# Power.net
KiCad netlist of a schematic drawn in EAGLE
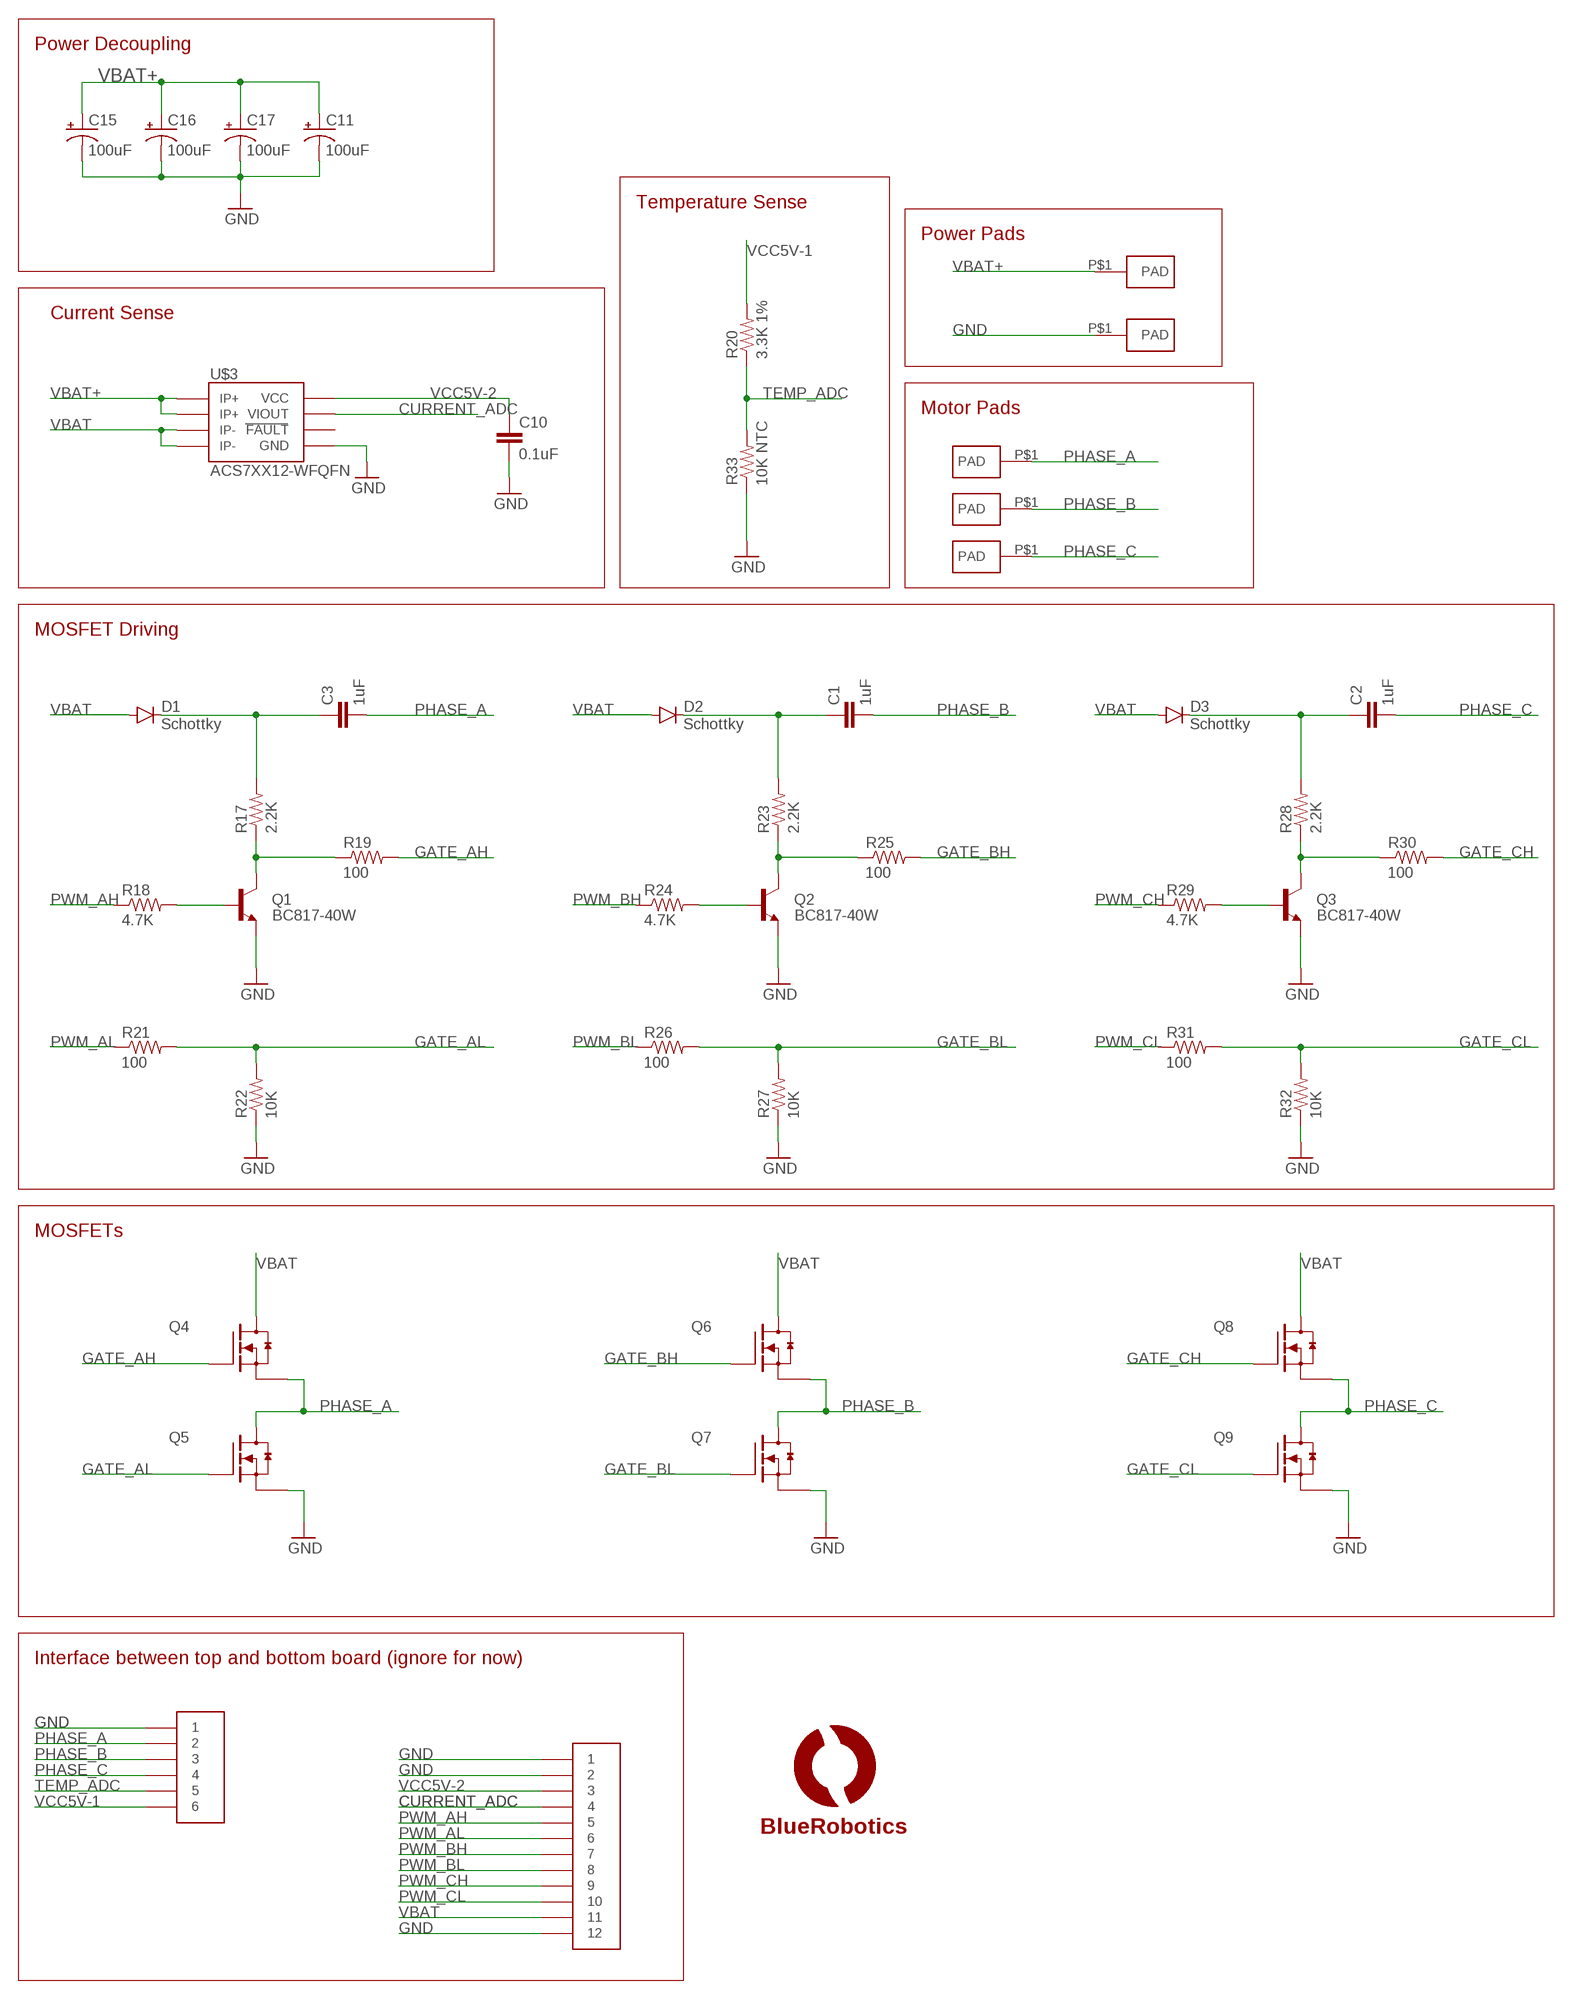
[diagram p0: schematic, sheet 1]

(export (version "E")
  (design (tool "Eeschema 10.0.6"))
  (components
    (comp (ref "C1")
      (value "1uF")
      (footprint "eagle-import:0805")
      (libsource (lib "eagle-import") (part "CAP0805"))
    )
    (comp (ref "C2")
      (value "1uF")
      (footprint "eagle-import:0805")
      (libsource (lib "eagle-import") (part "CAP0805"))
    )
    (comp (ref "C3")
      (value "1uF")
      (footprint "eagle-import:0805")
      (libsource (lib "eagle-import") (part "CAP0805"))
    )
    (comp (ref "C10")
      (value "0.1uF")
      (footprint "eagle-import:0603-CAP")
      (libsource (lib "eagle-import") (part "CAP0603-CAP"))
    )
    (comp (ref "C11")
      (value "100uF")
      (footprint "eagle-import:EIA7343")
      (libsource (lib "eagle-import") (part "CAP_POL7343"))
    )
    (comp (ref "C15")
      (value "100uF")
      (footprint "eagle-import:EIA7343")
      (libsource (lib "eagle-import") (part "CAP_POL7343"))
    )
    (comp (ref "C16")
      (value "100uF")
      (footprint "eagle-import:EIA7343")
      (libsource (lib "eagle-import") (part "CAP_POL7343"))
    )
    (comp (ref "C17")
      (value "100uF")
      (footprint "eagle-import:EIA7343")
      (libsource (lib "eagle-import") (part "CAP_POL7343"))
    )
    (comp (ref "D1")
      (value "Schottky")
      (footprint "eagle-import:SOD-323")
      (libsource (lib "eagle-import") (part "DIODESOD"))
    )
    (comp (ref "D2")
      (value "Schottky")
      (footprint "eagle-import:SOD-323")
      (libsource (lib "eagle-import") (part "DIODESOD"))
    )
    (comp (ref "D3")
      (value "Schottky")
      (footprint "eagle-import:SOD-323")
      (libsource (lib "eagle-import") (part "DIODESOD"))
    )
    (comp (ref "Q1")
      (value "BC817-40W")
      (footprint "eagle-import:SOT23")
      (libsource (lib "eagle-import") (part "TRANSISTOR_NPNSOT23"))
    )
    (comp (ref "Q2")
      (value "BC817-40W")
      (footprint "eagle-import:SOT23")
      (libsource (lib "eagle-import") (part "TRANSISTOR_NPNSOT23"))
    )
    (comp (ref "Q3")
      (value "BC817-40W")
      (footprint "eagle-import:SOT23")
      (libsource (lib "eagle-import") (part "TRANSISTOR_NPNSOT23"))
    )
    (comp (ref "Q4")
      (value "SI7370")
      (footprint "eagle-import:POWERPAK-SO-08")
      (libsource (lib "eagle-import") (part "SI7370"))
    )
    (comp (ref "Q5")
      (value "SI7370")
      (footprint "eagle-import:POWERPAK-SO-08")
      (libsource (lib "eagle-import") (part "SI7370"))
    )
    (comp (ref "Q6")
      (value "SI7370")
      (footprint "eagle-import:POWERPAK-SO-08")
      (libsource (lib "eagle-import") (part "SI7370"))
    )
    (comp (ref "Q7")
      (value "SI7370")
      (footprint "eagle-import:POWERPAK-SO-08")
      (libsource (lib "eagle-import") (part "SI7370"))
    )
    (comp (ref "Q8")
      (value "SI7370")
      (footprint "eagle-import:POWERPAK-SO-08")
      (libsource (lib "eagle-import") (part "SI7370"))
    )
    (comp (ref "Q9")
      (value "SI7370")
      (footprint "eagle-import:POWERPAK-SO-08")
      (libsource (lib "eagle-import") (part "SI7370"))
    )
    (comp (ref "R17")
      (value "2.2K")
      (footprint "eagle-import:0603-RES")
      (libsource (lib "eagle-import") (part "33KOHM1/10W1%(0603)"))
    )
    (comp (ref "R18")
      (value "4.7K")
      (footprint "eagle-import:0603-RES")
      (libsource (lib "eagle-import") (part "33KOHM1/10W1%(0603)"))
    )
    (comp (ref "R19")
      (value "100")
      (footprint "eagle-import:0603-RES")
      (libsource (lib "eagle-import") (part "33KOHM1/10W1%(0603)"))
    )
    (comp (ref "R20")
      (value "3.3K 1%")
      (footprint "eagle-import:0603-RES")
      (libsource (lib "eagle-import") (part "33KOHM1/10W1%(0603)"))
    )
    (comp (ref "R21")
      (value "100")
      (footprint "eagle-import:0603-RES")
      (libsource (lib "eagle-import") (part "33KOHM1/10W1%(0603)"))
    )
    (comp (ref "R22")
      (value "10K")
      (footprint "eagle-import:0603-RES")
      (libsource (lib "eagle-import") (part "33KOHM1/10W1%(0603)"))
    )
    (comp (ref "R23")
      (value "2.2K")
      (footprint "eagle-import:0603-RES")
      (libsource (lib "eagle-import") (part "33KOHM1/10W1%(0603)"))
    )
    (comp (ref "R24")
      (value "4.7K")
      (footprint "eagle-import:0603-RES")
      (libsource (lib "eagle-import") (part "33KOHM1/10W1%(0603)"))
    )
    (comp (ref "R25")
      (value "100")
      (footprint "eagle-import:0603-RES")
      (libsource (lib "eagle-import") (part "33KOHM1/10W1%(0603)"))
    )
    (comp (ref "R26")
      (value "100")
      (footprint "eagle-import:0603-RES")
      (libsource (lib "eagle-import") (part "33KOHM1/10W1%(0603)"))
    )
    (comp (ref "R27")
      (value "10K")
      (footprint "eagle-import:0603-RES")
      (libsource (lib "eagle-import") (part "33KOHM1/10W1%(0603)"))
    )
    (comp (ref "R28")
      (value "2.2K")
      (footprint "eagle-import:0603-RES")
      (libsource (lib "eagle-import") (part "33KOHM1/10W1%(0603)"))
    )
    (comp (ref "R29")
      (value "4.7K")
      (footprint "eagle-import:0603-RES")
      (libsource (lib "eagle-import") (part "33KOHM1/10W1%(0603)"))
    )
    (comp (ref "R30")
      (value "100")
      (footprint "eagle-import:0603-RES")
      (libsource (lib "eagle-import") (part "33KOHM1/10W1%(0603)"))
    )
    (comp (ref "R31")
      (value "100")
      (footprint "eagle-import:0603-RES")
      (libsource (lib "eagle-import") (part "33KOHM1/10W1%(0603)"))
    )
    (comp (ref "R32")
      (value "10K")
      (footprint "eagle-import:0603-RES")
      (libsource (lib "eagle-import") (part "33KOHM1/10W1%(0603)"))
    )
    (comp (ref "R33")
      (value "10K NTC")
      (footprint "eagle-import:0603-RES")
      (libsource (lib "eagle-import") (part "33KOHM1/10W1%(0603)"))
    )
    (comp (ref "U$1")
      (value "PADPTH-MED")
      (footprint "eagle-import:PAD-PTH-MED-1")
      (libsource (lib "eagle-import") (part "PADPTH-MED"))
    )
    (comp (ref "U$2")
      (value "PADPTH-MED")
      (footprint "eagle-import:PAD-PTH-MED-1")
      (libsource (lib "eagle-import") (part "PADPTH-MED"))
    )
    (comp (ref "U$3")
      (value "ACS7XX12-WFQFN")
      (footprint "eagle-import:12-WFQFN")
      (libsource (lib "eagle-import") (part "ACS7XX12-WFQFN"))
    )
    (comp (ref "U$4")
      (value "HEADER-62MM")
      (footprint "eagle-import:HEADER-2MM-6POS")
      (libsource (lib "eagle-import") (part "HEADER-62MM"))
    )
    (comp (ref "U$5")
      (value "PAD18AWG")
      (footprint "eagle-import:PAD-PTH-18AWG-1")
      (libsource (lib "eagle-import") (part "PAD18AWG"))
    )
    (comp (ref "U$6")
      (value "PAD18AWG")
      (footprint "eagle-import:PAD-PTH-18AWG-1")
      (libsource (lib "eagle-import") (part "PAD18AWG"))
    )
    (comp (ref "U$7")
      (value "PAD18AWG")
      (footprint "eagle-import:PAD-PTH-18AWG-1")
      (libsource (lib "eagle-import") (part "PAD18AWG"))
    )
    (comp (ref "U$8")
      (value "HEADER-122MM")
      (footprint "eagle-import:HEADER-2MM-12POS")
      (libsource (lib "eagle-import") (part "HEADER-122MM"))
    )
    (comp (ref "U$9")
      (value "LOGOBR-LOGO-S")
      (footprint "eagle-import:BR-LOGO-SMALL")
      (libsource (lib "eagle-import") (part "LOGOBR-LOGO-S"))
    )
  )
  (nets
    (net (code "1") (name "/CURRENT_ADC") (class "Default")
      (node (ref "U$3") (pin "VIOUT") (pinfunction "VIOUT_VIOUT") (pintype "bidirectional"))
      (node (ref "U$8") (pin "P$4") (pinfunction "4_P$4") (pintype "bidirectional"))
    )
    (net (code "2") (name "/GATE_AH") (class "Default")
      (node (ref "Q4") (pin "4") (pinfunction "G_4") (pintype "passive"))
      (node (ref "R19") (pin "2") (pinfunction "2_2") (pintype "passive"))
    )
    (net (code "3") (name "/GATE_AL") (class "Default")
      (node (ref "Q5") (pin "4") (pinfunction "G_4") (pintype "passive"))
      (node (ref "R21") (pin "2") (pinfunction "2_2") (pintype "passive"))
      (node (ref "R22") (pin "2") (pinfunction "2_2") (pintype "passive"))
    )
    (net (code "4") (name "/GATE_BH") (class "Default")
      (node (ref "Q6") (pin "4") (pinfunction "G_4") (pintype "passive"))
      (node (ref "R25") (pin "2") (pinfunction "2_2") (pintype "passive"))
    )
    (net (code "5") (name "/GATE_BL") (class "Default")
      (node (ref "Q7") (pin "4") (pinfunction "G_4") (pintype "passive"))
      (node (ref "R26") (pin "2") (pinfunction "2_2") (pintype "passive"))
      (node (ref "R27") (pin "2") (pinfunction "2_2") (pintype "passive"))
    )
    (net (code "6") (name "/GATE_CH") (class "Default")
      (node (ref "Q8") (pin "4") (pinfunction "G_4") (pintype "passive"))
      (node (ref "R30") (pin "2") (pinfunction "2_2") (pintype "passive"))
    )
    (net (code "7") (name "/GATE_CL") (class "Default")
      (node (ref "Q9") (pin "4") (pinfunction "G_4") (pintype "passive"))
      (node (ref "R31") (pin "2") (pinfunction "2_2") (pintype "passive"))
      (node (ref "R32") (pin "2") (pinfunction "2_2") (pintype "passive"))
    )
    (net (code "8") (name "/PHASE_A") (class "Default")
      (node (ref "C3") (pin "2") (pinfunction "2_2") (pintype "passive"))
      (node (ref "Q4") (pin "3") (pinfunction "S3_3") (pintype "passive"))
      (node (ref "Q5") (pin "5-8") (pinfunction "D_5-8") (pintype "passive"))
      (node (ref "U$4") (pin "P$2") (pinfunction "2_P$2") (pintype "bidirectional"))
      (node (ref "U$5") (pin "P$1") (pinfunction "PAD_P$1") (pintype "bidirectional"))
    )
    (net (code "9") (name "/PHASE_B") (class "Default")
      (node (ref "C1") (pin "2") (pinfunction "2_2") (pintype "passive"))
      (node (ref "Q6") (pin "3") (pinfunction "S3_3") (pintype "passive"))
      (node (ref "Q7") (pin "5-8") (pinfunction "D_5-8") (pintype "passive"))
      (node (ref "U$4") (pin "P$3") (pinfunction "3_P$3") (pintype "bidirectional"))
      (node (ref "U$6") (pin "P$1") (pinfunction "PAD_P$1") (pintype "bidirectional"))
    )
    (net (code "10") (name "/PHASE_C") (class "Default")
      (node (ref "C2") (pin "2") (pinfunction "2_2") (pintype "passive"))
      (node (ref "Q8") (pin "3") (pinfunction "S3_3") (pintype "passive"))
      (node (ref "Q9") (pin "5-8") (pinfunction "D_5-8") (pintype "passive"))
      (node (ref "U$4") (pin "P$4") (pinfunction "4_P$4") (pintype "bidirectional"))
      (node (ref "U$7") (pin "P$1") (pinfunction "PAD_P$1") (pintype "bidirectional"))
    )
    (net (code "11") (name "/PWM_AH") (class "Default")
      (node (ref "R18") (pin "1") (pinfunction "1_1") (pintype "passive"))
      (node (ref "U$8") (pin "P$5") (pinfunction "5_P$5") (pintype "bidirectional"))
    )
    (net (code "12") (name "/PWM_AL") (class "Default")
      (node (ref "R21") (pin "1") (pinfunction "1_1") (pintype "passive"))
      (node (ref "U$8") (pin "P$6") (pinfunction "6_P$6") (pintype "bidirectional"))
    )
    (net (code "13") (name "/PWM_BH") (class "Default")
      (node (ref "R24") (pin "1") (pinfunction "1_1") (pintype "passive"))
      (node (ref "U$8") (pin "P$7") (pinfunction "7_P$7") (pintype "bidirectional"))
    )
    (net (code "14") (name "/PWM_BL") (class "Default")
      (node (ref "R26") (pin "1") (pinfunction "1_1") (pintype "passive"))
      (node (ref "U$8") (pin "P$8") (pinfunction "8_P$8") (pintype "bidirectional"))
    )
    (net (code "15") (name "/PWM_CH") (class "Default")
      (node (ref "R29") (pin "1") (pinfunction "1_1") (pintype "passive"))
      (node (ref "U$8") (pin "P$9") (pinfunction "9_P$9") (pintype "bidirectional"))
    )
    (net (code "16") (name "/PWM_CL") (class "Default")
      (node (ref "R31") (pin "1") (pinfunction "1_1") (pintype "passive"))
      (node (ref "U$8") (pin "P$10") (pinfunction "10_P$10") (pintype "bidirectional"))
    )
    (net (code "17") (name "/TEMP_ADC") (class "Default")
      (node (ref "R20") (pin "1") (pinfunction "1_1") (pintype "passive"))
      (node (ref "R33") (pin "2") (pinfunction "2_2") (pintype "passive"))
      (node (ref "U$4") (pin "P$5") (pinfunction "5_P$5") (pintype "bidirectional"))
    )
    (net (code "18") (name "/VBAT") (class "Default")
      (node (ref "D1") (pin "A") (pinfunction "A_A") (pintype "passive"))
      (node (ref "D2") (pin "A") (pinfunction "A_A") (pintype "passive"))
      (node (ref "D3") (pin "A") (pinfunction "A_A") (pintype "passive"))
      (node (ref "Q4") (pin "5-8") (pinfunction "D_5-8") (pintype "passive"))
      (node (ref "Q6") (pin "5-8") (pinfunction "D_5-8") (pintype "passive"))
      (node (ref "Q8") (pin "5-8") (pinfunction "D_5-8") (pintype "passive"))
      (node (ref "U$3") (pin "IP-1") (pinfunction "IP-1_IP-1") (pintype "bidirectional"))
      (node (ref "U$3") (pin "IP-2") (pinfunction "IP-2_IP-2") (pintype "bidirectional"))
      (node (ref "U$8") (pin "P$11") (pinfunction "11_P$11") (pintype "bidirectional"))
    )
    (net (code "19") (name "/VBAT+") (class "Default")
      (node (ref "C11") (pin "A") (pinfunction "+_A") (pintype "passive"))
      (node (ref "C15") (pin "A") (pinfunction "+_A") (pintype "passive"))
      (node (ref "C16") (pin "A") (pinfunction "+_A") (pintype "passive"))
      (node (ref "C17") (pin "A") (pinfunction "+_A") (pintype "passive"))
      (node (ref "U$1") (pin "P$1") (pinfunction "PAD_P$1") (pintype "bidirectional"))
      (node (ref "U$3") (pin "IP+1") (pinfunction "IP+1_IP+1") (pintype "bidirectional"))
      (node (ref "U$3") (pin "IP+2") (pinfunction "IP+2_IP+2") (pintype "bidirectional"))
    )
    (net (code "20") (name "/VCC5V-1") (class "Default")
      (node (ref "R20") (pin "2") (pinfunction "2_2") (pintype "passive"))
      (node (ref "U$4") (pin "P$6") (pinfunction "6_P$6") (pintype "bidirectional"))
    )
    (net (code "21") (name "/VCC5V-2") (class "Default")
      (node (ref "C10") (pin "1") (pinfunction "1_1") (pintype "passive"))
      (node (ref "U$3") (pin "VCC") (pinfunction "VCC_VCC") (pintype "power_in"))
      (node (ref "U$8") (pin "P$3") (pinfunction "3_P$3") (pintype "bidirectional"))
    )
    (net (code "22") (name "GND") (class "Default")
      (node (ref "C10") (pin "2") (pinfunction "2_2") (pintype "passive"))
      (node (ref "C11") (pin "C") (pinfunction "-_C") (pintype "passive"))
      (node (ref "C15") (pin "C") (pinfunction "-_C") (pintype "passive"))
      (node (ref "C16") (pin "C") (pinfunction "-_C") (pintype "passive"))
      (node (ref "C17") (pin "C") (pinfunction "-_C") (pintype "passive"))
      (node (ref "Q1") (pin "2") (pinfunction "E_2") (pintype "passive"))
      (node (ref "Q2") (pin "2") (pinfunction "E_2") (pintype "passive"))
      (node (ref "Q3") (pin "2") (pinfunction "E_2") (pintype "passive"))
      (node (ref "Q5") (pin "3") (pinfunction "S3_3") (pintype "passive"))
      (node (ref "Q7") (pin "3") (pinfunction "S3_3") (pintype "passive"))
      (node (ref "Q9") (pin "3") (pinfunction "S3_3") (pintype "passive"))
      (node (ref "R22") (pin "1") (pinfunction "1_1") (pintype "passive"))
      (node (ref "R27") (pin "1") (pinfunction "1_1") (pintype "passive"))
      (node (ref "R32") (pin "1") (pinfunction "1_1") (pintype "passive"))
      (node (ref "R33") (pin "1") (pinfunction "1_1") (pintype "passive"))
      (node (ref "U$2") (pin "P$1") (pinfunction "PAD_P$1") (pintype "bidirectional"))
      (node (ref "U$3") (pin "GND") (pinfunction "GND_GND") (pintype "power_in"))
      (node (ref "U$4") (pin "P$1") (pinfunction "1_P$1") (pintype "bidirectional"))
      (node (ref "U$8") (pin "P$1") (pinfunction "1_P$1") (pintype "bidirectional"))
      (node (ref "U$8") (pin "P$12") (pinfunction "12_P$12") (pintype "bidirectional"))
      (node (ref "U$8") (pin "P$2") (pinfunction "2_P$2") (pintype "bidirectional"))
    )
    (net (code "23") (name "Net-(C1-Pad1)") (class "Default")
      (node (ref "C1") (pin "1") (pinfunction "1_1") (pintype "passive"))
      (node (ref "D2") (pin "C") (pinfunction "C_C") (pintype "passive"))
      (node (ref "R23") (pin "2") (pinfunction "2_2") (pintype "passive"))
    )
    (net (code "24") (name "Net-(C2-Pad1)") (class "Default")
      (node (ref "C2") (pin "1") (pinfunction "1_1") (pintype "passive"))
      (node (ref "D3") (pin "C") (pinfunction "C_C") (pintype "passive"))
      (node (ref "R28") (pin "2") (pinfunction "2_2") (pintype "passive"))
    )
    (net (code "25") (name "Net-(C3-Pad1)") (class "Default")
      (node (ref "C3") (pin "1") (pinfunction "1_1") (pintype "passive"))
      (node (ref "D1") (pin "C") (pinfunction "C_C") (pintype "passive"))
      (node (ref "R17") (pin "2") (pinfunction "2_2") (pintype "passive"))
    )
    (net (code "26") (name "Net-(Q1-B)") (class "Default")
      (node (ref "Q1") (pin "1") (pinfunction "B_1") (pintype "passive"))
      (node (ref "R18") (pin "2") (pinfunction "2_2") (pintype "passive"))
    )
    (net (code "27") (name "Net-(Q1-C)") (class "Default")
      (node (ref "Q1") (pin "3") (pinfunction "C_3") (pintype "passive"))
      (node (ref "R17") (pin "1") (pinfunction "1_1") (pintype "passive"))
      (node (ref "R19") (pin "1") (pinfunction "1_1") (pintype "passive"))
    )
    (net (code "28") (name "Net-(Q2-B)") (class "Default")
      (node (ref "Q2") (pin "1") (pinfunction "B_1") (pintype "passive"))
      (node (ref "R24") (pin "2") (pinfunction "2_2") (pintype "passive"))
    )
    (net (code "29") (name "Net-(Q2-C)") (class "Default")
      (node (ref "Q2") (pin "3") (pinfunction "C_3") (pintype "passive"))
      (node (ref "R23") (pin "1") (pinfunction "1_1") (pintype "passive"))
      (node (ref "R25") (pin "1") (pinfunction "1_1") (pintype "passive"))
    )
    (net (code "30") (name "Net-(Q3-B)") (class "Default")
      (node (ref "Q3") (pin "1") (pinfunction "B_1") (pintype "passive"))
      (node (ref "R29") (pin "2") (pinfunction "2_2") (pintype "passive"))
    )
    (net (code "31") (name "Net-(Q3-C)") (class "Default")
      (node (ref "Q3") (pin "3") (pinfunction "C_3") (pintype "passive"))
      (node (ref "R28") (pin "1") (pinfunction "1_1") (pintype "passive"))
      (node (ref "R30") (pin "1") (pinfunction "1_1") (pintype "passive"))
    )
    (net (code "32") (name "unconnected-(Q4-S1-Pad1)") (class "Default")
      (node (ref "Q4") (pin "1") (pinfunction "S1_1") (pintype "passive"))
    )
    (net (code "33") (name "unconnected-(Q4-S2-Pad2)") (class "Default")
      (node (ref "Q4") (pin "2") (pinfunction "S2_2") (pintype "passive"))
    )
    (net (code "34") (name "unconnected-(Q5-S1-Pad1)") (class "Default")
      (node (ref "Q5") (pin "1") (pinfunction "S1_1") (pintype "passive"))
    )
    (net (code "35") (name "unconnected-(Q5-S2-Pad2)") (class "Default")
      (node (ref "Q5") (pin "2") (pinfunction "S2_2") (pintype "passive"))
    )
    (net (code "36") (name "unconnected-(Q6-S1-Pad1)") (class "Default")
      (node (ref "Q6") (pin "1") (pinfunction "S1_1") (pintype "passive"))
    )
    (net (code "37") (name "unconnected-(Q6-S2-Pad2)") (class "Default")
      (node (ref "Q6") (pin "2") (pinfunction "S2_2") (pintype "passive"))
    )
    (net (code "38") (name "unconnected-(Q7-S1-Pad1)") (class "Default")
      (node (ref "Q7") (pin "1") (pinfunction "S1_1") (pintype "passive"))
    )
    (net (code "39") (name "unconnected-(Q7-S2-Pad2)") (class "Default")
      (node (ref "Q7") (pin "2") (pinfunction "S2_2") (pintype "passive"))
    )
    (net (code "40") (name "unconnected-(Q8-S1-Pad1)") (class "Default")
      (node (ref "Q8") (pin "1") (pinfunction "S1_1") (pintype "passive"))
    )
    (net (code "41") (name "unconnected-(Q8-S2-Pad2)") (class "Default")
      (node (ref "Q8") (pin "2") (pinfunction "S2_2") (pintype "passive"))
    )
    (net (code "42") (name "unconnected-(Q9-S1-Pad1)") (class "Default")
      (node (ref "Q9") (pin "1") (pinfunction "S1_1") (pintype "passive"))
    )
    (net (code "43") (name "unconnected-(Q9-S2-Pad2)") (class "Default")
      (node (ref "Q9") (pin "2") (pinfunction "S2_2") (pintype "passive"))
    )
    (net (code "44") (name "unconnected-(U$3-PadFAULT)") (class "Default")
      (node (ref "U$3") (pin "FAULT") (pinfunction "FAULT_FAULT") (pintype "bidirectional"))
    )
  )
)
